# fa3d_Buck.net
KiCad netlist of a schematic drawn in EAGLE
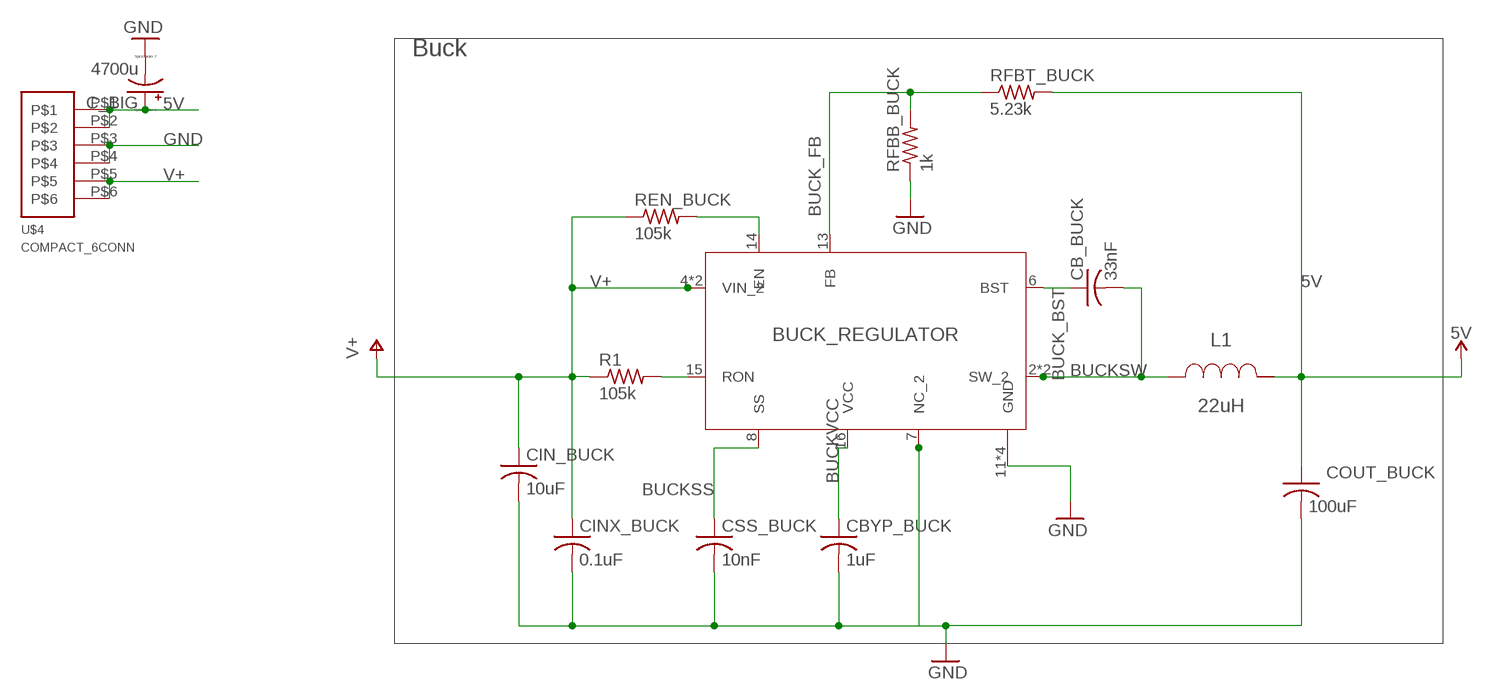
[diagram p0: schematic, sheet 1]

(export (version "E")
  (design (tool "Eeschema 10.0.6"))
  (components
    (comp (ref "BUCK_REGULATOR")
      (value "BUCK")
      (footprint "eagle-import:MXA20A")
      (fields
        (field (name "MANUFACTURER_PART_NUMBER") "LM3102MHXNOPB")
        (field (name "PARTNO") "LM3102MH/NOPB")
      )
      (libsource (lib "eagle-import") (part "LM3102MHX/NOPB"))
    )
    (comp (ref "CBYP_BUCK")
      (value "1uF")
      (footprint "eagle-import:C0603")
      (fields (field (name "PARTNO") "CL10A105KB8NNNC"))
      (libsource (lib "eagle-import") (part "resistor_348_C-USC0603"))
    )
    (comp (ref "CB_BUCK")
      (value "33nF")
      (footprint "eagle-import:C0603")
      (fields (field (name "PARTNO") "885012206092"))
      (libsource (lib "eagle-import") (part "resistor_348_C-USC0603"))
    )
    (comp (ref "CINX_BUCK")
      (value "0.1uF")
      (footprint "eagle-import:C0603")
      (fields (field (name "PARTNO") "CL10B104KB8NNNC"))
      (libsource (lib "eagle-import") (part "resistor_348_C-USC0603"))
    )
    (comp (ref "CIN_BUCK")
      (value "10uF")
      (footprint "eagle-import:C1206")
      (fields (field (name "PARTNO") "GRM188R6YA106MA73D"))
      (libsource (lib "eagle-import") (part "C-USC1206"))
    )
    (comp (ref "COUT_BUCK")
      (value "100uF")
      (footprint "eagle-import:C1206")
      (fields (field (name "PARTNO") "CL31A107MQHNNNE"))
      (libsource (lib "eagle-import") (part "resistor_348_C-USC1206"))
    )
    (comp (ref "CSS_BUCK")
      (value "10nF")
      (footprint "eagle-import:C0603")
      (fields (field (name "PARTNO") "885012206089"))
      (libsource (lib "eagle-import") (part "resistor_348_C-USC0603"))
    )
    (comp (ref "C_BIG")
      (value "4700u")
      (footprint "eagle-import:TT5D11")
      (fields (field (name "PARTNO") "UVR0J472MHD"))
      (libsource (lib "eagle-import") (part "CPOL-USTT5D11"))
    )
    (comp (ref "L1")
      (value "22uH")
      (footprint "eagle-import:SDR1307")
      (fields
        (field (name "MANUFACTURER_PART_NUMBER") "SDR1307220ML")
        (field (name "PARTNO") "SDR1307-220ML")
      )
      (libsource (lib "eagle-import") (part "SDR1307-220ML"))
    )
    (comp (ref "R1")
      (value "105k")
      (footprint "eagle-import:R0603")
      (fields (field (name "PARTNO") "RMCF0603FT105K"))
      (libsource (lib "eagle-import") (part "R-US_R0603"))
    )
    (comp (ref "REN_BUCK")
      (value "105k")
      (footprint "eagle-import:R0603")
      (fields (field (name "PARTNO") "RMCF0603FT105K"))
      (libsource (lib "eagle-import") (part "R-US_R0603"))
    )
    (comp (ref "RFBB_BUCK")
      (value "1k")
      (footprint "eagle-import:R0603")
      (fields (field (name "PARTNO") "RMCF0603JJ1K00"))
      (libsource (lib "eagle-import") (part "R-US_R0603"))
    )
    (comp (ref "RFBT_BUCK")
      (value "5.23k")
      (footprint "eagle-import:R0603")
      (fields (field (name "PARTNO") "RMCF0603FT5K23"))
      (libsource (lib "eagle-import") (part "R-US_R0603"))
    )
    (comp (ref "U$4")
      (value "COMPACT_6CONN")
      (footprint "eagle-import:COMPACT_6CONN")
      (libsource (lib "eagle-import") (part "COMPACT_6CONN"))
    )
  )
  (nets
    (net (code "1") (name "5V") (class "Default")
      (node (ref "COUT_BUCK") (pin "1") (pinfunction "1_1") (pintype "passive"))
      (node (ref "C_BIG") (pin "+") (pinfunction "+_+") (pintype "passive"))
      (node (ref "L1") (pin "2") (pinfunction "2_2") (pintype "passive"))
      (node (ref "RFBT_BUCK") (pin "2") (pinfunction "2_2") (pintype "passive"))
      (node (ref "U$4") (pin "P$1") (pinfunction "P$1_P$1") (pintype "bidirectional"))
      (node (ref "U$4") (pin "P$2") (pinfunction "P$2_P$2") (pintype "bidirectional"))
    )
    (net (code "2") (name "BUCKSS") (class "Default")
      (node (ref "BUCK_REGULATOR") (pin "8") (pinfunction "SS_8") (pintype "passive"))
      (node (ref "CSS_BUCK") (pin "1") (pinfunction "1_1") (pintype "passive"))
    )
    (net (code "3") (name "BUCKSW") (class "Default")
      (node (ref "BUCK_REGULATOR") (pin "2") (pinfunction "SW_2_2") (pintype "passive"))
      (node (ref "BUCK_REGULATOR") (pin "3") (pinfunction "SW_2_3") (pintype "passive"))
      (node (ref "CB_BUCK") (pin "2") (pinfunction "2_2") (pintype "passive"))
      (node (ref "L1") (pin "1") (pinfunction "1_1") (pintype "passive"))
    )
    (net (code "4") (name "BUCKVCC") (class "Default")
      (node (ref "BUCK_REGULATOR") (pin "16") (pinfunction "VCC_16") (pintype "passive"))
      (node (ref "CBYP_BUCK") (pin "1") (pinfunction "1_1") (pintype "passive"))
    )
    (net (code "5") (name "BUCK_BST") (class "Default")
      (node (ref "BUCK_REGULATOR") (pin "6") (pinfunction "BST_6") (pintype "passive"))
      (node (ref "CB_BUCK") (pin "1") (pinfunction "1_1") (pintype "passive"))
    )
    (net (code "6") (name "BUCK_FB") (class "Default")
      (node (ref "BUCK_REGULATOR") (pin "13") (pinfunction "FB_13") (pintype "passive"))
      (node (ref "RFBB_BUCK") (pin "2") (pinfunction "2_2") (pintype "passive"))
      (node (ref "RFBT_BUCK") (pin "1") (pinfunction "1_1") (pintype "passive"))
    )
    (net (code "7") (name "GND") (class "Default")
      (node (ref "BUCK_REGULATOR") (pin "11") (pinfunction "GND_11") (pintype "bidirectional"))
      (node (ref "BUCK_REGULATOR") (pin "17") (pinfunction "GND_17") (pintype "bidirectional"))
      (node (ref "BUCK_REGULATOR") (pin "18") (pinfunction "GND_18") (pintype "bidirectional"))
      (node (ref "BUCK_REGULATOR") (pin "21") (pinfunction "GND_21") (pintype "bidirectional"))
      (node (ref "BUCK_REGULATOR") (pin "7") (pinfunction "NC_2_7") (pintype "passive"))
      (node (ref "CBYP_BUCK") (pin "2") (pinfunction "2_2") (pintype "passive"))
      (node (ref "CINX_BUCK") (pin "2") (pinfunction "2_2") (pintype "passive"))
      (node (ref "CIN_BUCK") (pin "2") (pinfunction "2_2") (pintype "passive"))
      (node (ref "COUT_BUCK") (pin "2") (pinfunction "2_2") (pintype "passive"))
      (node (ref "CSS_BUCK") (pin "2") (pinfunction "2_2") (pintype "passive"))
      (node (ref "C_BIG") (pin "-") (pinfunction "-_-") (pintype "passive"))
      (node (ref "RFBB_BUCK") (pin "1") (pinfunction "1_1") (pintype "passive"))
      (node (ref "U$4") (pin "P$3") (pinfunction "P$3_P$3") (pintype "bidirectional"))
      (node (ref "U$4") (pin "P$4") (pinfunction "P$4_P$4") (pintype "bidirectional"))
    )
    (net (code "8") (name "Net-(BUCK_REGULATOR-EN)") (class "Default")
      (node (ref "BUCK_REGULATOR") (pin "14") (pinfunction "EN_14") (pintype "passive"))
      (node (ref "REN_BUCK") (pin "2") (pinfunction "2_2") (pintype "passive"))
    )
    (net (code "9") (name "Net-(BUCK_REGULATOR-RON)") (class "Default")
      (node (ref "BUCK_REGULATOR") (pin "15") (pinfunction "RON_15") (pintype "passive"))
      (node (ref "R1") (pin "2") (pinfunction "2_2") (pintype "passive"))
    )
    (net (code "10") (name "V+") (class "Default")
      (node (ref "BUCK_REGULATOR") (pin "4") (pinfunction "VIN_2_4") (pintype "passive"))
      (node (ref "BUCK_REGULATOR") (pin "5") (pinfunction "VIN_2_5") (pintype "passive"))
      (node (ref "CINX_BUCK") (pin "1") (pinfunction "1_1") (pintype "passive"))
      (node (ref "CIN_BUCK") (pin "1") (pinfunction "1_1") (pintype "passive"))
      (node (ref "R1") (pin "1") (pinfunction "1_1") (pintype "passive"))
      (node (ref "REN_BUCK") (pin "1") (pinfunction "1_1") (pintype "passive"))
      (node (ref "U$4") (pin "P$5") (pinfunction "P$5_P$5") (pintype "bidirectional"))
      (node (ref "U$4") (pin "P$6") (pinfunction "P$6_P$6") (pintype "bidirectional"))
    )
  )
)
